# APDS-9801.net
KiCad netlist of a schematic drawn in EAGLE
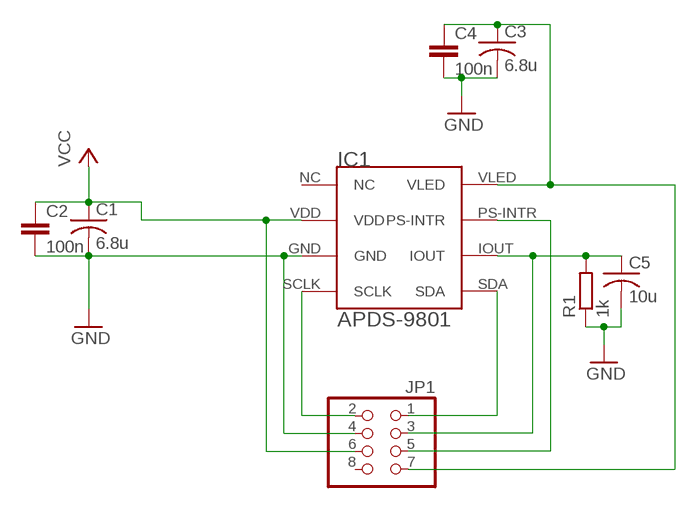
[diagram p0: schematic, sheet 1]

(export (version "E")
  (design (tool "Eeschema 10.0.6"))
  (components
    (comp (ref "C1")
      (value "6.8u")
      (footprint "eagle-import:C025-024X044")
      (libsource (lib "eagle-import") (part "C-US025-024X044"))
    )
    (comp (ref "C2")
      (value "100n")
      (footprint "eagle-import:C0805")
      (libsource (lib "eagle-import") (part "C-EUC0805"))
    )
    (comp (ref "C3")
      (value "6.8u")
      (footprint "eagle-import:C025-024X044")
      (libsource (lib "eagle-import") (part "C-US025-024X044"))
    )
    (comp (ref "C4")
      (value "100n")
      (footprint "eagle-import:C0805")
      (libsource (lib "eagle-import") (part "C-EUC0805"))
    )
    (comp (ref "C5")
      (value "10u")
      (footprint "eagle-import:C025-024X044")
      (libsource (lib "eagle-import") (part "C-US025-024X044"))
    )
    (comp (ref "IC1")
      (value "APDS-9801")
      (footprint "eagle-import:APDS-9801")
      (libsource (lib "eagle-import") (part "APDS-9801"))
    )
    (comp (ref "JP1")
      (value "PINHD-2X4")
      (footprint "eagle-import:2X04")
      (libsource (lib "eagle-import") (part "PINHD-2X4"))
    )
    (comp (ref "R1")
      (value "1k")
      (footprint "eagle-import:M0805")
      (libsource (lib "eagle-import") (part "R-EU_M0805"))
    )
  )
  (nets
    (net (code "1") (name "GND") (class "Default")
      (node (ref "C1") (pin "2") (pinfunction "2_2") (pintype "passive"))
      (node (ref "C2") (pin "2") (pinfunction "2_2") (pintype "passive"))
      (node (ref "C3") (pin "2") (pinfunction "2_2") (pintype "passive"))
      (node (ref "C4") (pin "2") (pinfunction "2_2") (pintype "passive"))
      (node (ref "C5") (pin "2") (pinfunction "2_2") (pintype "passive"))
      (node (ref "IC1") (pin "GND") (pinfunction "GND_GND") (pintype "power_in"))
      (node (ref "JP1") (pin "4") (pinfunction "4_4") (pintype "passive"))
      (node (ref "R1") (pin "1") (pinfunction "1_1") (pintype "passive"))
    )
    (net (code "2") (name "Net-(C3-Pad1)") (class "Default")
      (node (ref "C3") (pin "1") (pinfunction "1_1") (pintype "passive"))
      (node (ref "C4") (pin "1") (pinfunction "1_1") (pintype "passive"))
      (node (ref "IC1") (pin "VLED") (pinfunction "VLED_VLED") (pintype "power_in"))
      (node (ref "JP1") (pin "7") (pinfunction "7_7") (pintype "passive"))
    )
    (net (code "3") (name "Net-(C5-Pad1)") (class "Default")
      (node (ref "C5") (pin "1") (pinfunction "1_1") (pintype "passive"))
      (node (ref "IC1") (pin "IOUT") (pinfunction "IOUT_IOUT") (pintype "input"))
      (node (ref "JP1") (pin "3") (pinfunction "3_3") (pintype "passive"))
      (node (ref "R1") (pin "2") (pinfunction "2_2") (pintype "passive"))
    )
    (net (code "4") (name "Net-(IC1-PadPS-INTR)") (class "Default")
      (node (ref "IC1") (pin "PS-INTR") (pinfunction "PS-INTR_PS-INTR") (pintype "output"))
      (node (ref "JP1") (pin "5") (pinfunction "5_5") (pintype "passive"))
    )
    (net (code "5") (name "Net-(IC1-PadSCLK)") (class "Default")
      (node (ref "IC1") (pin "SCLK") (pinfunction "SCLK_SCLK") (pintype "bidirectional"))
      (node (ref "JP1") (pin "2") (pinfunction "2_2") (pintype "passive"))
    )
    (net (code "6") (name "Net-(IC1-PadSDA)") (class "Default")
      (node (ref "IC1") (pin "SDA") (pinfunction "SDA_SDA") (pintype "bidirectional"))
      (node (ref "JP1") (pin "1") (pinfunction "1_1") (pintype "passive"))
    )
    (net (code "7") (name "VCC") (class "Default")
      (node (ref "C1") (pin "1") (pinfunction "1_1") (pintype "passive"))
      (node (ref "C2") (pin "1") (pinfunction "1_1") (pintype "passive"))
      (node (ref "IC1") (pin "VDD") (pinfunction "VDD_VDD") (pintype "power_in"))
      (node (ref "JP1") (pin "6") (pinfunction "6_6") (pintype "passive"))
    )
    (net (code "8") (name "unconnected-(IC1-PadNC)") (class "Default")
      (node (ref "IC1") (pin "NC") (pinfunction "NC_NC") (pintype "no_connect"))
    )
    (net (code "9") (name "unconnected-(JP1-Pad8)") (class "Default")
      (node (ref "JP1") (pin "8") (pinfunction "8_8") (pintype "passive"))
    )
  )
)
